# shield.net
KiCad netlist of a schematic drawn in EAGLE
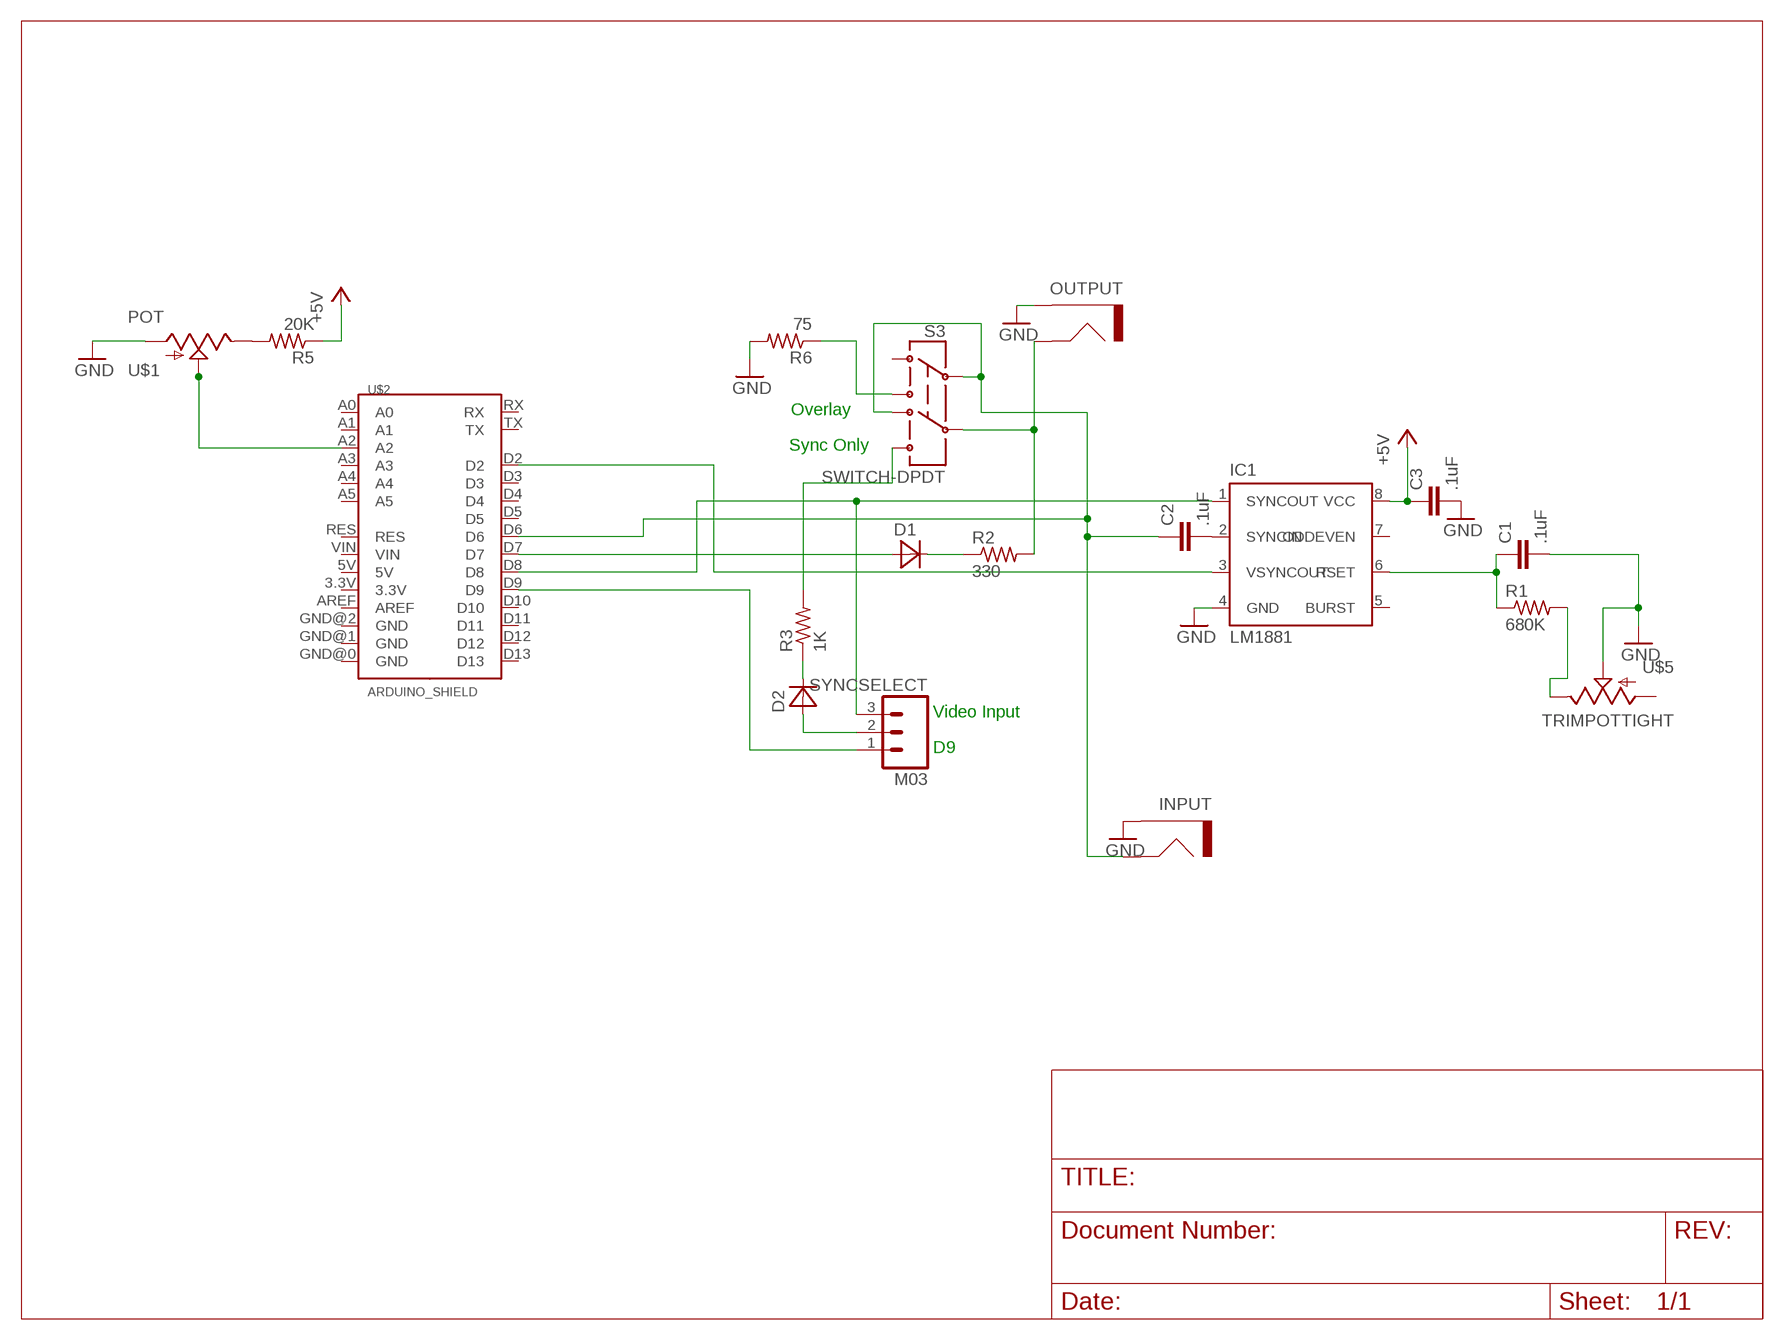
[diagram p0: schematic, sheet 1]

(export (version "E")
  (design (tool "Eeschema 10.0.6"))
  (components
    (comp (ref "C1")
      (value ".1uF")
      (footprint "eagle-import:CAP-CERAMIC-SMALL")
      (libsource (lib "eagle-import") (part "CAPSMALL"))
    )
    (comp (ref "C2")
      (value ".1uF")
      (footprint "eagle-import:CAP-CERAMIC-SMALL")
      (libsource (lib "eagle-import") (part "CAPSMALL"))
    )
    (comp (ref "C3")
      (value ".1uF")
      (footprint "eagle-import:CAP-CERAMIC-SMALL")
      (libsource (lib "eagle-import") (part "CAPSMALL"))
    )
    (comp (ref "D1")
      (value "1N4148")
      (footprint "eagle-import:D35-10")
      (libsource (lib "eagle-import") (part "1N4148"))
    )
    (comp (ref "D2")
      (value "1N4148")
      (footprint "eagle-import:D35-10")
      (libsource (lib "eagle-import") (part "1N4148"))
    )
    (comp (ref "IC1")
      (value "LM1881")
      (footprint "eagle-import:DIL08")
      (libsource (lib "eagle-import") (part "LM1881"))
    )
    (comp (ref "INPUT")
      (value "RCAJACK")
      (footprint "eagle-import:RCA")
      (libsource (lib "eagle-import") (part "RCAJACK"))
    )
    (comp (ref "OUTPUT")
      (value "RCAJACK")
      (footprint "eagle-import:RCA")
      (libsource (lib "eagle-import") (part "RCAJACK"))
    )
    (comp (ref "R1")
      (value "680K")
      (footprint "eagle-import:0207_10")
      (libsource (lib "eagle-import") (part "R-US"))
    )
    (comp (ref "R2")
      (value "330")
      (footprint "eagle-import:0207_10")
      (libsource (lib "eagle-import") (part "R-US"))
    )
    (comp (ref "R3")
      (value "1K")
      (footprint "eagle-import:0207_10")
      (libsource (lib "eagle-import") (part "R-US"))
    )
    (comp (ref "R5")
      (value "20K")
      (footprint "eagle-import:0207_10")
      (libsource (lib "eagle-import") (part "R-US"))
    )
    (comp (ref "R6")
      (value "75")
      (footprint "eagle-import:0207_10")
      (libsource (lib "eagle-import") (part "R-US"))
    )
    (comp (ref "S3")
      (value "SWITCH-DPDT")
      (footprint "eagle-import:OS")
      (libsource (lib "eagle-import") (part "SWITCH-DPDT"))
    )
    (comp (ref "SYNCSELECT")
      (value "M03")
      (footprint "eagle-import:1X03")
      (libsource (lib "eagle-import") (part "M03"))
    )
    (comp (ref "U$1")
      (value "POT")
      (footprint "eagle-import:TRIMMERPOT")
      (libsource (lib "eagle-import") (part "POT"))
    )
    (comp (ref "U$2")
      (value "ARDUINO_SHIELD")
      (footprint "eagle-import:DUEMILANOVE_SHIELD")
      (libsource (lib "eagle-import") (part "ARDUINO_SHIELD"))
    )
    (comp (ref "U$5")
      (value "TRIMPOTTIGHT")
      (footprint "eagle-import:TRIM_POT_TIGHT")
      (libsource (lib "eagle-import") (part "TRIMPOTTIGHT"))
    )
  )
  (nets
    (net (code "1") (name "+5V") (class "Default")
      (node (ref "C3") (pin "1") (pinfunction "1_1") (pintype "passive"))
      (node (ref "IC1") (pin "8") (pinfunction "VCC_8") (pintype "power_in"))
      (node (ref "R5") (pin "1") (pinfunction "1_1") (pintype "passive"))
    )
    (net (code "2") (name "GND") (class "Default")
      (node (ref "C1") (pin "2") (pinfunction "2_2") (pintype "passive"))
      (node (ref "C3") (pin "2") (pinfunction "2_2") (pintype "passive"))
      (node (ref "IC1") (pin "4") (pinfunction "GND_4") (pintype "power_in"))
      (node (ref "INPUT") (pin "BARREL") (pinfunction "GND_BARREL") (pintype "bidirectional"))
      (node (ref "OUTPUT") (pin "BARREL") (pinfunction "GND_BARREL") (pintype "bidirectional"))
      (node (ref "R6") (pin "2") (pinfunction "2_2") (pintype "passive"))
      (node (ref "U$1") (pin "1") (pinfunction "1_1") (pintype "passive"))
      (node (ref "U$5") (pin "2") (pinfunction "2_2") (pintype "passive"))
    )
    (net (code "3") (name "Net-(D1-PadA)") (class "Default")
      (node (ref "D1") (pin "A") (pinfunction "A_A") (pintype "passive"))
      (node (ref "U$2") (pin "D7") (pinfunction "D7_D7") (pintype "bidirectional"))
    )
    (net (code "4") (name "Net-(D1-PadC)") (class "Default")
      (node (ref "D1") (pin "C") (pinfunction "C_C") (pintype "passive"))
      (node (ref "R2") (pin "1") (pinfunction "1_1") (pintype "passive"))
    )
    (net (code "5") (name "Net-(D2-PadC)") (class "Default")
      (node (ref "D2") (pin "C") (pinfunction "C_C") (pintype "passive"))
      (node (ref "R3") (pin "1") (pinfunction "1_1") (pintype "passive"))
    )
    (net (code "6") (name "Net-(IC1-RSET)") (class "Default")
      (node (ref "C1") (pin "1") (pinfunction "1_1") (pintype "passive"))
      (node (ref "IC1") (pin "6") (pinfunction "RSET_6") (pintype "output"))
      (node (ref "R1") (pin "1") (pinfunction "1_1") (pintype "passive"))
    )
    (net (code "7") (name "Net-(IC1-SYNCIN)") (class "Default")
      (node (ref "C2") (pin "2") (pinfunction "2_2") (pintype "passive"))
      (node (ref "IC1") (pin "2") (pinfunction "SYNCIN_2") (pintype "input"))
    )
    (net (code "8") (name "Net-(IC1-SYNCOUT)") (class "Default")
      (node (ref "IC1") (pin "1") (pinfunction "SYNCOUT_1") (pintype "output"))
      (node (ref "SYNCSELECT") (pin "3") (pinfunction "4_3") (pintype "passive"))
      (node (ref "U$2") (pin "D8") (pinfunction "D8_D8") (pintype "bidirectional"))
    )
    (net (code "9") (name "Net-(IC1-VSYNCOUT)") (class "Default")
      (node (ref "IC1") (pin "3") (pinfunction "VSYNCOUT_3") (pintype "output"))
      (node (ref "U$2") (pin "D2") (pinfunction "D2_D2") (pintype "bidirectional"))
    )
    (net (code "10") (name "Net-(INPUT-SIGNAL)") (class "Default")
      (node (ref "C2") (pin "1") (pinfunction "1_1") (pintype "passive"))
      (node (ref "INPUT") (pin "P$2") (pinfunction "SIGNAL_P$2") (pintype "bidirectional"))
      (node (ref "S3") (pin "2") (pinfunction "2_2") (pintype "bidirectional"))
      (node (ref "S3") (pin "4") (pinfunction "4_4") (pintype "bidirectional"))
      (node (ref "U$2") (pin "D6") (pinfunction "D6_D6") (pintype "bidirectional"))
    )
    (net (code "11") (name "Net-(OUTPUT-SIGNAL)") (class "Default")
      (node (ref "OUTPUT") (pin "P$2") (pinfunction "SIGNAL_P$2") (pintype "bidirectional"))
      (node (ref "R2") (pin "2") (pinfunction "2_2") (pintype "passive"))
      (node (ref "S3") (pin "5") (pinfunction "5_5") (pintype "bidirectional"))
    )
    (net (code "12") (name "Net-(R1-Pad2)") (class "Default")
      (node (ref "R1") (pin "2") (pinfunction "2_2") (pintype "passive"))
      (node (ref "U$5") (pin "3") (pinfunction "3_3") (pintype "passive"))
    )
    (net (code "13") (name "Net-(R3-Pad2)") (class "Default")
      (node (ref "R3") (pin "2") (pinfunction "2_2") (pintype "passive"))
      (node (ref "S3") (pin "6") (pinfunction "6_6") (pintype "bidirectional"))
    )
    (net (code "14") (name "Net-(R5-Pad2)") (class "Default")
      (node (ref "R5") (pin "2") (pinfunction "2_2") (pintype "passive"))
      (node (ref "U$1") (pin "3") (pinfunction "3_3") (pintype "passive"))
    )
    (net (code "15") (name "Net-(R6-Pad1)") (class "Default")
      (node (ref "R6") (pin "1") (pinfunction "1_1") (pintype "passive"))
      (node (ref "S3") (pin "3") (pinfunction "3_3") (pintype "bidirectional"))
    )
    (net (code "16") (name "Net-(SYNCSELECT-2)") (class "Default")
      (node (ref "SYNCSELECT") (pin "1") (pinfunction "2_1") (pintype "passive"))
      (node (ref "U$2") (pin "D9") (pinfunction "D9_D9") (pintype "bidirectional"))
    )
    (net (code "17") (name "Net-(SYNCSELECT-3)") (class "Default")
      (node (ref "D2") (pin "A") (pinfunction "A_A") (pintype "passive"))
      (node (ref "SYNCSELECT") (pin "2") (pinfunction "3_2") (pintype "passive"))
    )
    (net (code "18") (name "Net-(U$1-WIPER-Pad2)") (class "Default")
      (node (ref "U$1") (pin "2") (pinfunction "WIPER_2") (pintype "passive"))
      (node (ref "U$1") (pin "4") (pinfunction "WIPER_4") (pintype "passive"))
      (node (ref "U$2") (pin "A2") (pinfunction "A2_A2") (pintype "bidirectional"))
    )
    (net (code "19") (name "unconnected-(IC1-BURST-Pad5)") (class "Default")
      (node (ref "IC1") (pin "5") (pinfunction "BURST_5") (pintype "output"))
    )
    (net (code "20") (name "unconnected-(IC1-ODDEVEN-Pad7)") (class "Default")
      (node (ref "IC1") (pin "7") (pinfunction "ODDEVEN_7") (pintype "output"))
    )
    (net (code "21") (name "unconnected-(S3-Pad1)") (class "Default")
      (node (ref "S3") (pin "1") (pinfunction "1_1") (pintype "bidirectional"))
    )
    (net (code "22") (name "unconnected-(U$2-GND-PadGND@0)") (class "Default")
      (node (ref "U$2") (pin "GND@0") (pinfunction "GND_GND@0") (pintype "bidirectional"))
    )
    (net (code "23") (name "unconnected-(U$2-GND-PadGND@1)") (class "Default")
      (node (ref "U$2") (pin "GND@1") (pinfunction "GND_GND@1") (pintype "bidirectional"))
    )
    (net (code "24") (name "unconnected-(U$2-GND-PadGND@2)") (class "Default")
      (node (ref "U$2") (pin "GND@2") (pinfunction "GND_GND@2") (pintype "bidirectional"))
    )
    (net (code "25") (name "unconnected-(U$2-Pad3.3V)") (class "Default")
      (node (ref "U$2") (pin "3.3V") (pinfunction "3.3V_3.3V") (pintype "bidirectional"))
    )
    (net (code "26") (name "unconnected-(U$2-Pad5V)") (class "Default")
      (node (ref "U$2") (pin "5V") (pinfunction "5V_5V") (pintype "bidirectional"))
    )
    (net (code "27") (name "unconnected-(U$2-PadA0)") (class "Default")
      (node (ref "U$2") (pin "A0") (pinfunction "A0_A0") (pintype "bidirectional"))
    )
    (net (code "28") (name "unconnected-(U$2-PadA1)") (class "Default")
      (node (ref "U$2") (pin "A1") (pinfunction "A1_A1") (pintype "bidirectional"))
    )
    (net (code "29") (name "unconnected-(U$2-PadA3)") (class "Default")
      (node (ref "U$2") (pin "A3") (pinfunction "A3_A3") (pintype "bidirectional"))
    )
    (net (code "30") (name "unconnected-(U$2-PadA4)") (class "Default")
      (node (ref "U$2") (pin "A4") (pinfunction "A4_A4") (pintype "bidirectional"))
    )
    (net (code "31") (name "unconnected-(U$2-PadA5)") (class "Default")
      (node (ref "U$2") (pin "A5") (pinfunction "A5_A5") (pintype "bidirectional"))
    )
    (net (code "32") (name "unconnected-(U$2-PadAREF)") (class "Default")
      (node (ref "U$2") (pin "AREF") (pinfunction "AREF_AREF") (pintype "bidirectional"))
    )
    (net (code "33") (name "unconnected-(U$2-PadD3)") (class "Default")
      (node (ref "U$2") (pin "D3") (pinfunction "D3_D3") (pintype "bidirectional"))
    )
    (net (code "34") (name "unconnected-(U$2-PadD4)") (class "Default")
      (node (ref "U$2") (pin "D4") (pinfunction "D4_D4") (pintype "bidirectional"))
    )
    (net (code "35") (name "unconnected-(U$2-PadD5)") (class "Default")
      (node (ref "U$2") (pin "D5") (pinfunction "D5_D5") (pintype "bidirectional"))
    )
    (net (code "36") (name "unconnected-(U$2-PadD10)") (class "Default")
      (node (ref "U$2") (pin "D10") (pinfunction "D10_D10") (pintype "bidirectional"))
    )
    (net (code "37") (name "unconnected-(U$2-PadD11)") (class "Default")
      (node (ref "U$2") (pin "D11") (pinfunction "D11_D11") (pintype "bidirectional"))
    )
    (net (code "38") (name "unconnected-(U$2-PadD12)") (class "Default")
      (node (ref "U$2") (pin "D12") (pinfunction "D12_D12") (pintype "bidirectional"))
    )
    (net (code "39") (name "unconnected-(U$2-PadD13)") (class "Default")
      (node (ref "U$2") (pin "D13") (pinfunction "D13_D13") (pintype "bidirectional"))
    )
    (net (code "40") (name "unconnected-(U$2-PadRES)") (class "Default")
      (node (ref "U$2") (pin "RES") (pinfunction "RES_RES") (pintype "bidirectional"))
    )
    (net (code "41") (name "unconnected-(U$2-PadRX)") (class "Default")
      (node (ref "U$2") (pin "RX") (pinfunction "RX_RX") (pintype "bidirectional"))
    )
    (net (code "42") (name "unconnected-(U$2-PadTX)") (class "Default")
      (node (ref "U$2") (pin "TX") (pinfunction "TX_TX") (pintype "bidirectional"))
    )
    (net (code "43") (name "unconnected-(U$2-PadVIN)") (class "Default")
      (node (ref "U$2") (pin "VIN") (pinfunction "VIN_VIN") (pintype "bidirectional"))
    )
    (net (code "44") (name "unconnected-(U$5-Pad1)") (class "Default")
      (node (ref "U$5") (pin "1") (pinfunction "1_1") (pintype "passive"))
    )
  )
)
